# boitier_commande.net
KiCad netlist of a schematic drawn in Altium Designer
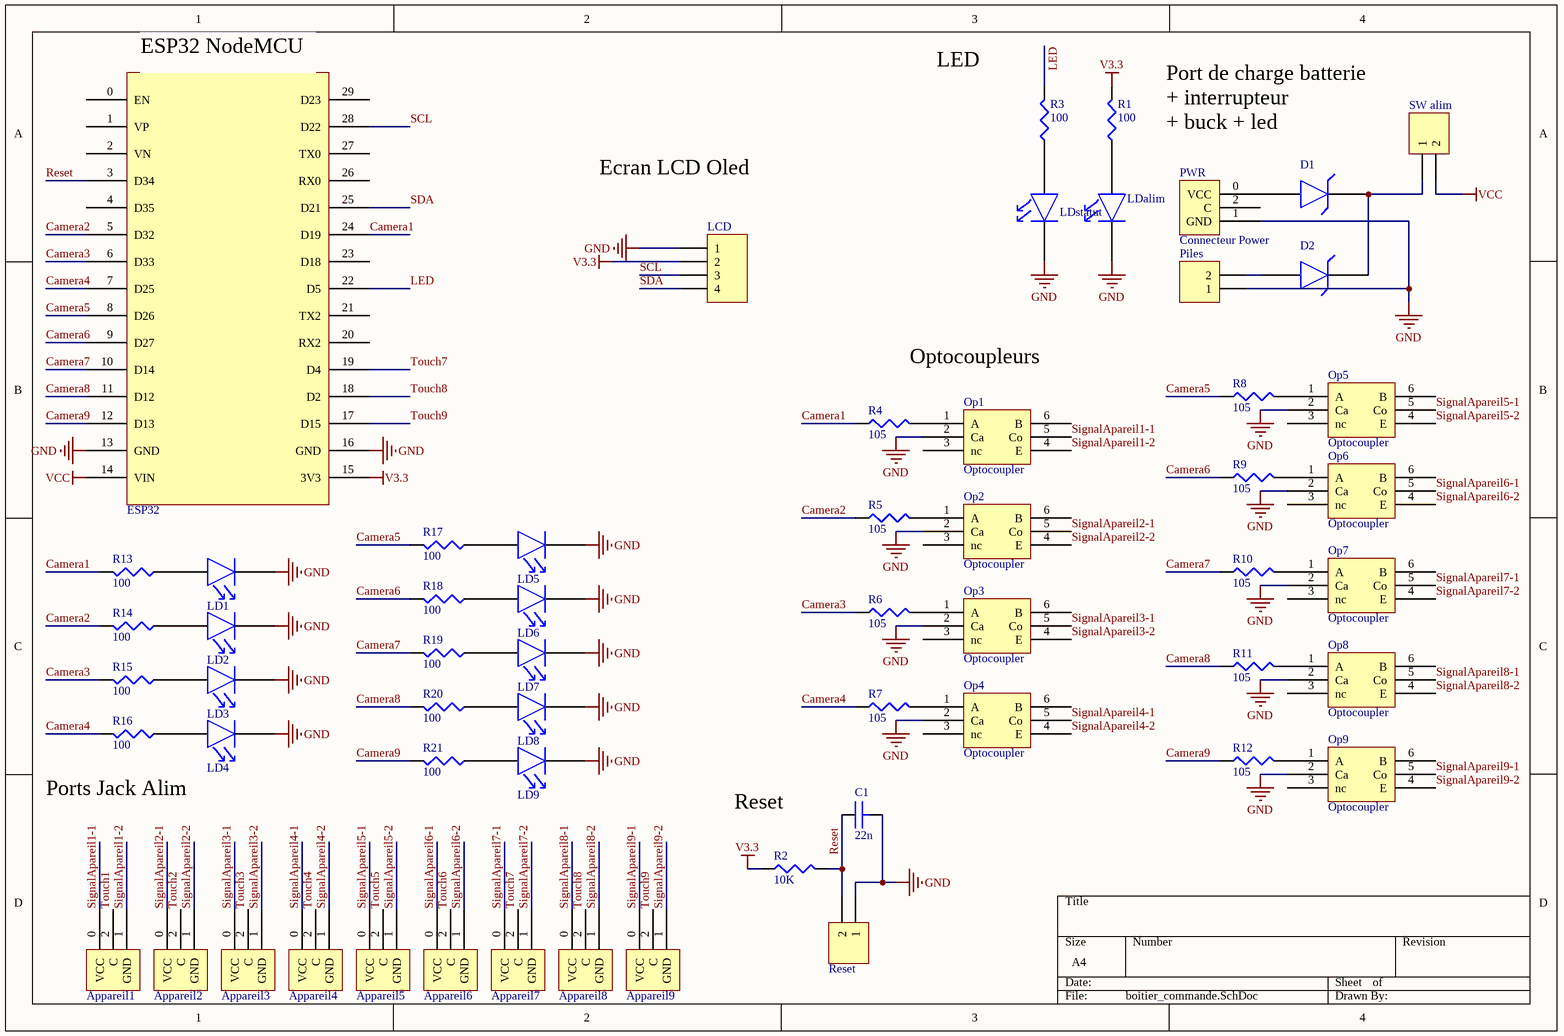
[diagram p0: boitier_commande.SchDoc]

(export (version "E")
  (design (tool "Eeschema 10.0.6"))
  (components
    (comp (ref "Appareil1")
      (value "Connecteur Power")
      (footprint "Connecteur Power")
      (libsource (lib "Jack Alim") (part "Connecteur Power"))
    )
    (comp (ref "Appareil2")
      (value "Connecteur Power")
      (footprint "Connecteur Power")
      (libsource (lib "Jack Alim") (part "Connecteur Power"))
    )
    (comp (ref "Appareil3")
      (value "Connecteur Power")
      (footprint "Connecteur Power")
      (libsource (lib "Jack Alim") (part "Connecteur Power"))
    )
    (comp (ref "Appareil4")
      (value "Connecteur Power")
      (footprint "Connecteur Power")
      (libsource (lib "Jack Alim") (part "Connecteur Power"))
    )
    (comp (ref "Appareil5")
      (value "Connecteur Power")
      (footprint "Connecteur Power")
      (libsource (lib "Jack Alim") (part "Connecteur Power"))
    )
    (comp (ref "Appareil6")
      (value "Connecteur Power")
      (footprint "Connecteur Power")
      (libsource (lib "Jack Alim") (part "Connecteur Power"))
    )
    (comp (ref "Appareil7")
      (value "Connecteur Power")
      (footprint "Connecteur Power")
      (libsource (lib "Jack Alim") (part "Connecteur Power"))
    )
    (comp (ref "Appareil8")
      (value "Connecteur Power")
      (footprint "Connecteur Power")
      (libsource (lib "Jack Alim") (part "Connecteur Power"))
    )
    (comp (ref "Appareil9")
      (value "Connecteur Power")
      (footprint "Connecteur Power")
      (libsource (lib "Jack Alim") (part "Connecteur Power"))
    )
    (comp (ref "C1")
      (value "22n")
      (footprint "RAD0.1")
      (description "capacité non polarisée")
      (fields (field (name "Comment") "CAP"))
      (libsource (lib "ISEN_basics") (part "CAP"))
    )
    (comp (ref "D1")
      (value "comment")
      (footprint "DIODE0.4")
      (description "diode schottky standard")
      (libsource (lib "ISEN_basics") (part "DIODE_schottky"))
    )
    (comp (ref "D2")
      (value "comment")
      (footprint "DIODE0.4")
      (description "diode schottky standard")
      (libsource (lib "ISEN_basics") (part "DIODE_schottky"))
    )
    (comp (ref "ESP32")
      (value "ESP32devKit")
      (footprint "ESP32")
      (libsource (lib "ESP32") (part "ESP32devKit"))
    )
    (comp (ref "LCD")
      (value "OLED LCD")
      (footprint "HDR1X4")
      (description "Header, 4-Pin")
      (fields (field (name "PUBLISHER") "Altium Limited"))
      (libsource (lib "Miscellaneous Connectors") (part "Header 4"))
    )
    (comp (ref "LD1")
      (value "comment")
      (footprint "LED0805")
      (description "LED 5mm/3mm/CMS")
      (libsource (lib "ISEN_basics") (part "LED"))
    )
    (comp (ref "LD2")
      (value "comment")
      (footprint "LED0805")
      (description "LED 5mm/3mm/CMS")
      (libsource (lib "ISEN_basics") (part "LED"))
    )
    (comp (ref "LD3")
      (value "comment")
      (footprint "LED0805")
      (description "LED 5mm/3mm/CMS")
      (libsource (lib "ISEN_basics") (part "LED"))
    )
    (comp (ref "LD4")
      (value "comment")
      (footprint "LED0805")
      (description "LED 5mm/3mm/CMS")
      (libsource (lib "ISEN_basics") (part "LED"))
    )
    (comp (ref "LD5")
      (value "comment")
      (footprint "LED0805")
      (description "LED 5mm/3mm/CMS")
      (libsource (lib "ISEN_basics") (part "LED"))
    )
    (comp (ref "LD6")
      (value "comment")
      (footprint "LED0805")
      (description "LED 5mm/3mm/CMS")
      (libsource (lib "ISEN_basics") (part "LED"))
    )
    (comp (ref "LD7")
      (value "comment")
      (footprint "LED0805")
      (description "LED 5mm/3mm/CMS")
      (libsource (lib "ISEN_basics") (part "LED"))
    )
    (comp (ref "LD8")
      (value "comment")
      (footprint "LED0805")
      (description "LED 5mm/3mm/CMS")
      (libsource (lib "ISEN_basics") (part "LED"))
    )
    (comp (ref "LD9")
      (value "comment")
      (footprint "LED0805")
      (description "LED 5mm/3mm/CMS")
      (libsource (lib "ISEN_basics") (part "LED"))
    )
    (comp (ref "LDalim")
      (value "comment")
      (footprint "LED3")
      (description "LED 5mm/3mm/CMS")
      (libsource (lib "ISEN_basics") (part "LED"))
    )
    (comp (ref "LDstatut")
      (value "comment")
      (footprint "LED3")
      (description "LED 5mm/3mm/CMS")
      (libsource (lib "ISEN_basics") (part "LED"))
    )
    (comp (ref "Op1")
      (value "Optocoupler")
      (footprint "4N26")
      (libsource (lib "Optocoupleur") (part "Optocoupler"))
    )
    (comp (ref "Op2")
      (value "Optocoupler")
      (footprint "4N26")
      (libsource (lib "Optocoupleur") (part "Optocoupler"))
    )
    (comp (ref "Op3")
      (value "Optocoupler")
      (footprint "4N26")
      (libsource (lib "Optocoupleur") (part "Optocoupler"))
    )
    (comp (ref "Op4")
      (value "Optocoupler")
      (footprint "4N26")
      (libsource (lib "Optocoupleur") (part "Optocoupler"))
    )
    (comp (ref "Op5")
      (value "Optocoupler")
      (footprint "4N26")
      (libsource (lib "Optocoupleur") (part "Optocoupler"))
    )
    (comp (ref "Op6")
      (value "Optocoupler")
      (footprint "4N26")
      (libsource (lib "Optocoupleur") (part "Optocoupler"))
    )
    (comp (ref "Op7")
      (value "Optocoupler")
      (footprint "4N26")
      (libsource (lib "Optocoupleur") (part "Optocoupler"))
    )
    (comp (ref "Op8")
      (value "Optocoupler")
      (footprint "4N26")
      (libsource (lib "Optocoupleur") (part "Optocoupler"))
    )
    (comp (ref "Op9")
      (value "Optocoupler")
      (footprint "4N26")
      (libsource (lib "Optocoupleur") (part "Optocoupler"))
    )
    (comp (ref "Piles")
      (value "Header 2")
      (footprint "HDR1X2")
      (description "Header, 2-Pin")
      (fields (field (name "PUBLISHER") "Altium Limited"))
      (libsource (lib "") (part "Header 2_1"))
    )
    (comp (ref "PWR")
      (value "Connecteur Power")
      (footprint "Connecteur Power")
      (libsource (lib "") (part "Connecteur Power_1"))
    )
    (comp (ref "R1")
      (value "100")
      (footprint "AXIAL0.4")
      (description "resistance")
      (fields (field (name "Comment") "RES"))
      (libsource (lib "ISEN_basics") (part "RES"))
    )
    (comp (ref "R2")
      (value "10K")
      (footprint "AXIAL0.4")
      (description "resistance")
      (fields (field (name "Comment") "RES"))
      (libsource (lib "ISEN_basics") (part "RES"))
    )
    (comp (ref "R3")
      (value "100")
      (footprint "AXIAL0.4")
      (description "resistance")
      (fields (field (name "Comment") "RES"))
      (libsource (lib "ISEN_basics") (part "RES"))
    )
    (comp (ref "R4")
      (value "105")
      (footprint "AXIAL0.4")
      (description "resistance")
      (fields (field (name "Comment") "RES"))
      (libsource (lib "ISEN_basics") (part "RES"))
    )
    (comp (ref "R5")
      (value "105")
      (footprint "AXIAL0.4")
      (description "resistance")
      (fields (field (name "Comment") "RES"))
      (libsource (lib "ISEN_basics") (part "RES"))
    )
    (comp (ref "R6")
      (value "105")
      (footprint "AXIAL0.4")
      (description "resistance")
      (fields (field (name "Comment") "RES"))
      (libsource (lib "ISEN_basics") (part "RES"))
    )
    (comp (ref "R7")
      (value "105")
      (footprint "AXIAL0.4")
      (description "resistance")
      (fields (field (name "Comment") "RES"))
      (libsource (lib "ISEN_basics") (part "RES"))
    )
    (comp (ref "R8")
      (value "105")
      (footprint "AXIAL0.4")
      (description "resistance")
      (fields (field (name "Comment") "RES"))
      (libsource (lib "ISEN_basics") (part "RES"))
    )
    (comp (ref "R9")
      (value "105")
      (footprint "AXIAL0.4")
      (description "resistance")
      (fields (field (name "Comment") "RES"))
      (libsource (lib "ISEN_basics") (part "RES"))
    )
    (comp (ref "R10")
      (value "105")
      (footprint "AXIAL0.4")
      (description "resistance")
      (fields (field (name "Comment") "RES"))
      (libsource (lib "ISEN_basics") (part "RES"))
    )
    (comp (ref "R11")
      (value "105")
      (footprint "AXIAL0.4")
      (description "resistance")
      (fields (field (name "Comment") "RES"))
      (libsource (lib "ISEN_basics") (part "RES"))
    )
    (comp (ref "R12")
      (value "105")
      (footprint "AXIAL0.4")
      (description "resistance")
      (fields (field (name "Comment") "RES"))
      (libsource (lib "ISEN_basics") (part "RES"))
    )
    (comp (ref "R13")
      (value "100")
      (footprint "0805")
      (description "resistance")
      (fields (field (name "Comment") "RES"))
      (libsource (lib "ISEN_basics") (part "RES"))
    )
    (comp (ref "R14")
      (value "100")
      (footprint "0805")
      (description "resistance")
      (fields (field (name "Comment") "RES"))
      (libsource (lib "ISEN_basics") (part "RES"))
    )
    (comp (ref "R15")
      (value "100")
      (footprint "0805")
      (description "resistance")
      (fields (field (name "Comment") "RES"))
      (libsource (lib "ISEN_basics") (part "RES"))
    )
    (comp (ref "R16")
      (value "100")
      (footprint "0805")
      (description "resistance")
      (fields (field (name "Comment") "RES"))
      (libsource (lib "ISEN_basics") (part "RES"))
    )
    (comp (ref "R17")
      (value "100")
      (footprint "0805")
      (description "resistance")
      (fields (field (name "Comment") "RES"))
      (libsource (lib "ISEN_basics") (part "RES"))
    )
    (comp (ref "R18")
      (value "100")
      (footprint "0805")
      (description "resistance")
      (fields (field (name "Comment") "RES"))
      (libsource (lib "ISEN_basics") (part "RES"))
    )
    (comp (ref "R19")
      (value "100")
      (footprint "0805")
      (description "resistance")
      (fields (field (name "Comment") "RES"))
      (libsource (lib "ISEN_basics") (part "RES"))
    )
    (comp (ref "R20")
      (value "100")
      (footprint "0805")
      (description "resistance")
      (fields (field (name "Comment") "RES"))
      (libsource (lib "ISEN_basics") (part "RES"))
    )
    (comp (ref "R21")
      (value "100")
      (footprint "0805")
      (description "resistance")
      (fields (field (name "Comment") "RES"))
      (libsource (lib "ISEN_basics") (part "RES"))
    )
    (comp (ref "Reset")
      (value "Header 2")
      (footprint "HDR1X2")
      (description "Header, 2-Pin")
      (fields (field (name "PUBLISHER") "Altium Limited"))
      (libsource (lib "") (part "Header 2_2"))
    )
    (comp (ref "SW alim")
      (value "Header 2")
      (footprint "HDR1X2")
      (description "Header, 2-Pin")
      (fields (field (name "PUBLISHER") "Altium Limited"))
      (libsource (lib "Miscellaneous Connectors") (part "Header 2"))
    )
  )
  (nets
    (net (code "1") (name "/Camera1") (class "Default")
      (node (ref "ESP32") (pin "24") (pinfunction "D19_24") (pintype "passive"))
      (node (ref "R13") (pin "2") (pintype "passive"))
      (node (ref "R4") (pin "1") (pintype "passive"))
    )
    (net (code "2") (name "/Camera2") (class "Default")
      (node (ref "ESP32") (pin "5") (pinfunction "D32_5") (pintype "passive"))
      (node (ref "R14") (pin "2") (pintype "passive"))
      (node (ref "R5") (pin "1") (pintype "passive"))
    )
    (net (code "3") (name "/Camera3") (class "Default")
      (node (ref "ESP32") (pin "6") (pinfunction "D33_6") (pintype "passive"))
      (node (ref "R15") (pin "2") (pintype "passive"))
      (node (ref "R6") (pin "1") (pintype "passive"))
    )
    (net (code "4") (name "/Camera4") (class "Default")
      (node (ref "ESP32") (pin "7") (pinfunction "D25_7") (pintype "passive"))
      (node (ref "R16") (pin "2") (pintype "passive"))
      (node (ref "R7") (pin "1") (pintype "passive"))
    )
    (net (code "5") (name "/Camera5") (class "Default")
      (node (ref "ESP32") (pin "8") (pinfunction "D26_8") (pintype "passive"))
      (node (ref "R17") (pin "2") (pintype "passive"))
      (node (ref "R8") (pin "1") (pintype "passive"))
    )
    (net (code "6") (name "/Camera6") (class "Default")
      (node (ref "ESP32") (pin "9") (pinfunction "D27_9") (pintype "passive"))
      (node (ref "R18") (pin "2") (pintype "passive"))
      (node (ref "R9") (pin "1") (pintype "passive"))
    )
    (net (code "7") (name "/Camera7") (class "Default")
      (node (ref "ESP32") (pin "10") (pinfunction "D14_10") (pintype "passive"))
      (node (ref "R10") (pin "1") (pintype "passive"))
      (node (ref "R19") (pin "2") (pintype "passive"))
    )
    (net (code "8") (name "/Camera8") (class "Default")
      (node (ref "ESP32") (pin "11") (pinfunction "D12_11") (pintype "passive"))
      (node (ref "R11") (pin "1") (pintype "passive"))
      (node (ref "R20") (pin "2") (pintype "passive"))
    )
    (net (code "9") (name "/Camera9") (class "Default")
      (node (ref "ESP32") (pin "12") (pinfunction "D13_12") (pintype "passive"))
      (node (ref "R12") (pin "1") (pintype "passive"))
      (node (ref "R21") (pin "2") (pintype "passive"))
    )
    (net (code "10") (name "/LED") (class "Default")
      (node (ref "ESP32") (pin "22") (pinfunction "D5_22") (pintype "passive"))
      (node (ref "R3") (pin "2") (pintype "passive"))
    )
    (net (code "11") (name "/Reset") (class "Default")
      (node (ref "C1") (pin "1") (pinfunction "1_1") (pintype "passive"))
      (node (ref "ESP32") (pin "3") (pinfunction "D34_3") (pintype "passive"))
      (node (ref "R2") (pin "2") (pintype "passive"))
      (node (ref "Reset") (pin "2") (pinfunction "2_2") (pintype "passive"))
    )
    (net (code "12") (name "/SCL") (class "Default")
      (node (ref "ESP32") (pin "28") (pinfunction "D22_28") (pintype "passive"))
      (node (ref "LCD") (pin "3") (pinfunction "3_3") (pintype "passive"))
    )
    (net (code "13") (name "/SDA") (class "Default")
      (node (ref "ESP32") (pin "25") (pinfunction "D21_25") (pintype "passive"))
      (node (ref "LCD") (pin "4") (pinfunction "4_4") (pintype "passive"))
    )
    (net (code "14") (name "/SignalApareil1-1") (class "Default")
      (node (ref "Appareil1") (pin "0") (pinfunction "VCC_0") (pintype "passive"))
      (node (ref "Op1") (pin "5") (pinfunction "Co_5") (pintype "passive"))
    )
    (net (code "15") (name "/SignalApareil1-2") (class "Default")
      (node (ref "Appareil1") (pin "1") (pinfunction "GND_1") (pintype "passive"))
      (node (ref "Op1") (pin "4") (pinfunction "E_4") (pintype "passive"))
    )
    (net (code "16") (name "/SignalApareil2-1") (class "Default")
      (node (ref "Appareil2") (pin "0") (pinfunction "VCC_0") (pintype "passive"))
      (node (ref "Op2") (pin "5") (pinfunction "Co_5") (pintype "passive"))
    )
    (net (code "17") (name "/SignalApareil2-2") (class "Default")
      (node (ref "Appareil2") (pin "1") (pinfunction "GND_1") (pintype "passive"))
      (node (ref "Op2") (pin "4") (pinfunction "E_4") (pintype "passive"))
    )
    (net (code "18") (name "/SignalApareil3-1") (class "Default")
      (node (ref "Appareil3") (pin "0") (pinfunction "VCC_0") (pintype "passive"))
      (node (ref "Op3") (pin "5") (pinfunction "Co_5") (pintype "passive"))
    )
    (net (code "19") (name "/SignalApareil3-2") (class "Default")
      (node (ref "Appareil3") (pin "1") (pinfunction "GND_1") (pintype "passive"))
      (node (ref "Op3") (pin "4") (pinfunction "E_4") (pintype "passive"))
    )
    (net (code "20") (name "/SignalApareil4-1") (class "Default")
      (node (ref "Appareil4") (pin "0") (pinfunction "VCC_0") (pintype "passive"))
      (node (ref "Op4") (pin "5") (pinfunction "Co_5") (pintype "passive"))
    )
    (net (code "21") (name "/SignalApareil4-2") (class "Default")
      (node (ref "Appareil4") (pin "1") (pinfunction "GND_1") (pintype "passive"))
      (node (ref "Op4") (pin "4") (pinfunction "E_4") (pintype "passive"))
    )
    (net (code "22") (name "/SignalApareil5-1") (class "Default")
      (node (ref "Appareil5") (pin "0") (pinfunction "VCC_0") (pintype "passive"))
      (node (ref "Op5") (pin "5") (pinfunction "Co_5") (pintype "passive"))
    )
    (net (code "23") (name "/SignalApareil5-2") (class "Default")
      (node (ref "Appareil5") (pin "1") (pinfunction "GND_1") (pintype "passive"))
      (node (ref "Op5") (pin "4") (pinfunction "E_4") (pintype "passive"))
    )
    (net (code "24") (name "/SignalApareil6-1") (class "Default")
      (node (ref "Appareil6") (pin "0") (pinfunction "VCC_0") (pintype "passive"))
      (node (ref "Op6") (pin "5") (pinfunction "Co_5") (pintype "passive"))
    )
    (net (code "25") (name "/SignalApareil6-2") (class "Default")
      (node (ref "Appareil6") (pin "1") (pinfunction "GND_1") (pintype "passive"))
      (node (ref "Op6") (pin "4") (pinfunction "E_4") (pintype "passive"))
    )
    (net (code "26") (name "/SignalApareil7-1") (class "Default")
      (node (ref "Appareil7") (pin "0") (pinfunction "VCC_0") (pintype "passive"))
      (node (ref "Op7") (pin "5") (pinfunction "Co_5") (pintype "passive"))
    )
    (net (code "27") (name "/SignalApareil7-2") (class "Default")
      (node (ref "Appareil7") (pin "1") (pinfunction "GND_1") (pintype "passive"))
      (node (ref "Op7") (pin "4") (pinfunction "E_4") (pintype "passive"))
    )
    (net (code "28") (name "/SignalApareil8-1") (class "Default")
      (node (ref "Appareil8") (pin "0") (pinfunction "VCC_0") (pintype "passive"))
      (node (ref "Op8") (pin "5") (pinfunction "Co_5") (pintype "passive"))
    )
    (net (code "29") (name "/SignalApareil8-2") (class "Default")
      (node (ref "Appareil8") (pin "1") (pinfunction "GND_1") (pintype "passive"))
      (node (ref "Op8") (pin "4") (pinfunction "E_4") (pintype "passive"))
    )
    (net (code "30") (name "/SignalApareil9-1") (class "Default")
      (node (ref "Appareil9") (pin "0") (pinfunction "VCC_0") (pintype "passive"))
      (node (ref "Op9") (pin "5") (pinfunction "Co_5") (pintype "passive"))
    )
    (net (code "31") (name "/SignalApareil9-2") (class "Default")
      (node (ref "Appareil9") (pin "1") (pinfunction "GND_1") (pintype "passive"))
      (node (ref "Op9") (pin "4") (pinfunction "E_4") (pintype "passive"))
    )
    (net (code "32") (name "/Touch1") (class "Default")
      (node (ref "Appareil1") (pin "2") (pinfunction "C_2") (pintype "passive"))
    )
    (net (code "33") (name "/Touch2") (class "Default")
      (node (ref "Appareil2") (pin "2") (pinfunction "C_2") (pintype "passive"))
    )
    (net (code "34") (name "/Touch3") (class "Default")
      (node (ref "Appareil3") (pin "2") (pinfunction "C_2") (pintype "passive"))
    )
    (net (code "35") (name "/Touch4") (class "Default")
      (node (ref "Appareil4") (pin "2") (pinfunction "C_2") (pintype "passive"))
    )
    (net (code "36") (name "/Touch5") (class "Default")
      (node (ref "Appareil5") (pin "2") (pinfunction "C_2") (pintype "passive"))
    )
    (net (code "37") (name "/Touch6") (class "Default")
      (node (ref "Appareil6") (pin "2") (pinfunction "C_2") (pintype "passive"))
    )
    (net (code "38") (name "/Touch7") (class "Default")
      (node (ref "Appareil7") (pin "2") (pinfunction "C_2") (pintype "passive"))
      (node (ref "ESP32") (pin "19") (pinfunction "D4_19") (pintype "passive"))
    )
    (net (code "39") (name "/Touch8") (class "Default")
      (node (ref "Appareil8") (pin "2") (pinfunction "C_2") (pintype "passive"))
      (node (ref "ESP32") (pin "18") (pinfunction "D2_18") (pintype "passive"))
    )
    (net (code "40") (name "/Touch9") (class "Default")
      (node (ref "Appareil9") (pin "2") (pinfunction "C_2") (pintype "passive"))
      (node (ref "ESP32") (pin "17") (pinfunction "D15_17") (pintype "passive"))
    )
    (net (code "41") (name "GND") (class "Default")
      (node (ref "C1") (pin "2") (pinfunction "2_2") (pintype "passive"))
      (node (ref "ESP32") (pin "13") (pinfunction "GND_13") (pintype "passive"))
      (node (ref "ESP32") (pin "16") (pinfunction "GND_16") (pintype "passive"))
      (node (ref "LCD") (pin "1") (pinfunction "1_1") (pintype "passive"))
      (node (ref "LD1") (pin "K") (pinfunction "10_K") (pintype "passive"))
      (node (ref "LD2") (pin "K") (pinfunction "10_K") (pintype "passive"))
      (node (ref "LD3") (pin "K") (pinfunction "10_K") (pintype "passive"))
      (node (ref "LD4") (pin "K") (pinfunction "10_K") (pintype "passive"))
      (node (ref "LD5") (pin "K") (pinfunction "10_K") (pintype "passive"))
      (node (ref "LD6") (pin "K") (pinfunction "10_K") (pintype "passive"))
      (node (ref "LD7") (pin "K") (pinfunction "10_K") (pintype "passive"))
      (node (ref "LD8") (pin "K") (pinfunction "10_K") (pintype "passive"))
      (node (ref "LD9") (pin "K") (pinfunction "10_K") (pintype "passive"))
      (node (ref "LDalim") (pin "K") (pinfunction "10_K") (pintype "passive"))
      (node (ref "LDstatut") (pin "K") (pinfunction "10_K") (pintype "passive"))
      (node (ref "Op1") (pin "2") (pinfunction "Ca_2") (pintype "passive"))
      (node (ref "Op2") (pin "2") (pinfunction "Ca_2") (pintype "passive"))
      (node (ref "Op3") (pin "2") (pinfunction "Ca_2") (pintype "passive"))
      (node (ref "Op4") (pin "2") (pinfunction "Ca_2") (pintype "passive"))
      (node (ref "Op5") (pin "2") (pinfunction "Ca_2") (pintype "passive"))
      (node (ref "Op6") (pin "2") (pinfunction "Ca_2") (pintype "passive"))
      (node (ref "Op7") (pin "2") (pinfunction "Ca_2") (pintype "passive"))
      (node (ref "Op8") (pin "2") (pinfunction "Ca_2") (pintype "passive"))
      (node (ref "Op9") (pin "2") (pinfunction "Ca_2") (pintype "passive"))
      (node (ref "PWR") (pin "1") (pinfunction "GND_1") (pintype "passive"))
      (node (ref "Piles") (pin "1") (pinfunction "1_1") (pintype "passive"))
      (node (ref "Reset") (pin "1") (pinfunction "1_1") (pintype "passive"))
    )
    (net (code "42") (name "Net-(D1-Pad2)") (class "Default")
      (node (ref "D1") (pin "2") (pinfunction "2_2") (pintype "passive"))
      (node (ref "D2") (pin "2") (pinfunction "2_2") (pintype "passive"))
      (node (ref "SW alim") (pin "1") (pinfunction "1_1") (pintype "passive"))
    )
    (net (code "43") (name "Net-(D2-Pad1)") (class "Default")
      (node (ref "D2") (pin "1") (pinfunction "1_1") (pintype "passive"))
      (node (ref "Piles") (pin "2") (pinfunction "2_2") (pintype "passive"))
    )
    (net (code "44") (name "Net-(LD1-8)") (class "Default")
      (node (ref "LD1") (pin "A") (pinfunction "8_A") (pintype "passive"))
      (node (ref "R13") (pin "1") (pintype "passive"))
    )
    (net (code "45") (name "Net-(LD2-8)") (class "Default")
      (node (ref "LD2") (pin "A") (pinfunction "8_A") (pintype "passive"))
      (node (ref "R14") (pin "1") (pintype "passive"))
    )
    (net (code "46") (name "Net-(LD3-8)") (class "Default")
      (node (ref "LD3") (pin "A") (pinfunction "8_A") (pintype "passive"))
      (node (ref "R15") (pin "1") (pintype "passive"))
    )
    (net (code "47") (name "Net-(LD4-8)") (class "Default")
      (node (ref "LD4") (pin "A") (pinfunction "8_A") (pintype "passive"))
      (node (ref "R16") (pin "1") (pintype "passive"))
    )
    (net (code "48") (name "Net-(LD5-8)") (class "Default")
      (node (ref "LD5") (pin "A") (pinfunction "8_A") (pintype "passive"))
      (node (ref "R17") (pin "1") (pintype "passive"))
    )
    (net (code "49") (name "Net-(LD6-8)") (class "Default")
      (node (ref "LD6") (pin "A") (pinfunction "8_A") (pintype "passive"))
      (node (ref "R18") (pin "1") (pintype "passive"))
    )
    (net (code "50") (name "Net-(LD7-8)") (class "Default")
      (node (ref "LD7") (pin "A") (pinfunction "8_A") (pintype "passive"))
      (node (ref "R19") (pin "1") (pintype "passive"))
    )
    (net (code "51") (name "Net-(LD8-8)") (class "Default")
      (node (ref "LD8") (pin "A") (pinfunction "8_A") (pintype "passive"))
      (node (ref "R20") (pin "1") (pintype "passive"))
    )
    (net (code "52") (name "Net-(LD9-8)") (class "Default")
      (node (ref "LD9") (pin "A") (pinfunction "8_A") (pintype "passive"))
      (node (ref "R21") (pin "1") (pintype "passive"))
    )
    (net (code "53") (name "Net-(LDalim-8)") (class "Default")
      (node (ref "LDalim") (pin "A") (pinfunction "8_A") (pintype "passive"))
      (node (ref "R1") (pin "1") (pintype "passive"))
    )
    (net (code "54") (name "Net-(LDstatut-8)") (class "Default")
      (node (ref "LDstatut") (pin "A") (pinfunction "8_A") (pintype "passive"))
      (node (ref "R3") (pin "1") (pintype "passive"))
    )
    (net (code "55") (name "Net-(Op1-A)") (class "Default")
      (node (ref "Op1") (pin "1") (pinfunction "A_1") (pintype "passive"))
      (node (ref "R4") (pin "2") (pintype "passive"))
    )
    (net (code "56") (name "Net-(Op2-A)") (class "Default")
      (node (ref "Op2") (pin "1") (pinfunction "A_1") (pintype "passive"))
      (node (ref "R5") (pin "2") (pintype "passive"))
    )
    (net (code "57") (name "Net-(Op3-A)") (class "Default")
      (node (ref "Op3") (pin "1") (pinfunction "A_1") (pintype "passive"))
      (node (ref "R6") (pin "2") (pintype "passive"))
    )
    (net (code "58") (name "Net-(Op4-A)") (class "Default")
      (node (ref "Op4") (pin "1") (pinfunction "A_1") (pintype "passive"))
      (node (ref "R7") (pin "2") (pintype "passive"))
    )
    (net (code "59") (name "Net-(Op5-A)") (class "Default")
      (node (ref "Op5") (pin "1") (pinfunction "A_1") (pintype "passive"))
      (node (ref "R8") (pin "2") (pintype "passive"))
    )
    (net (code "60") (name "Net-(Op6-A)") (class "Default")
      (node (ref "Op6") (pin "1") (pinfunction "A_1") (pintype "passive"))
      (node (ref "R9") (pin "2") (pintype "passive"))
    )
    (net (code "61") (name "Net-(Op7-A)") (class "Default")
      (node (ref "Op7") (pin "1") (pinfunction "A_1") (pintype "passive"))
      (node (ref "R10") (pin "2") (pintype "passive"))
    )
    (net (code "62") (name "Net-(Op8-A)") (class "Default")
      (node (ref "Op8") (pin "1") (pinfunction "A_1") (pintype "passive"))
      (node (ref "R11") (pin "2") (pintype "passive"))
    )
    (net (code "63") (name "Net-(Op9-A)") (class "Default")
      (node (ref "Op9") (pin "1") (pinfunction "A_1") (pintype "passive"))
      (node (ref "R12") (pin "2") (pintype "passive"))
    )
    (net (code "64") (name "Net-(PWR-VCC)") (class "Default")
      (node (ref "D1") (pin "1") (pinfunction "1_1") (pintype "passive"))
      (node (ref "PWR") (pin "0") (pinfunction "VCC_0") (pintype "passive"))
    )
    (net (code "65") (name "V3.3") (class "Default")
      (node (ref "ESP32") (pin "15") (pinfunction "3V3_15") (pintype "passive"))
      (node (ref "LCD") (pin "2") (pinfunction "2_2") (pintype "passive"))
      (node (ref "R1") (pin "2") (pintype "passive"))
      (node (ref "R2") (pin "1") (pintype "passive"))
    )
    (net (code "66") (name "VCC") (class "Default")
      (node (ref "ESP32") (pin "14") (pinfunction "VIN_14") (pintype "passive"))
      (node (ref "SW alim") (pin "2") (pinfunction "2_2") (pintype "passive"))
    )
    (net (code "67") (name "unconnected-(ESP32-D18-Pad23)") (class "Default")
      (node (ref "ESP32") (pin "23") (pinfunction "D18_23") (pintype "passive"))
    )
    (net (code "68") (name "unconnected-(ESP32-D23-Pad29)") (class "Default")
      (node (ref "ESP32") (pin "29") (pinfunction "D23_29") (pintype "passive"))
    )
    (net (code "69") (name "unconnected-(ESP32-D35-Pad4)") (class "Default")
      (node (ref "ESP32") (pin "4") (pinfunction "D35_4") (pintype "passive"))
    )
    (net (code "70") (name "unconnected-(ESP32-EN-Pad0)") (class "Default")
      (node (ref "ESP32") (pin "0") (pinfunction "EN_0") (pintype "passive"))
    )
    (net (code "71") (name "unconnected-(ESP32-RX0-Pad26)") (class "Default")
      (node (ref "ESP32") (pin "26") (pinfunction "RX0_26") (pintype "passive"))
    )
    (net (code "72") (name "unconnected-(ESP32-RX2-Pad20)") (class "Default")
      (node (ref "ESP32") (pin "20") (pinfunction "RX2_20") (pintype "passive"))
    )
    (net (code "73") (name "unconnected-(ESP32-TX0-Pad27)") (class "Default")
      (node (ref "ESP32") (pin "27") (pinfunction "TX0_27") (pintype "passive"))
    )
    (net (code "74") (name "unconnected-(ESP32-TX2-Pad21)") (class "Default")
      (node (ref "ESP32") (pin "21") (pinfunction "TX2_21") (pintype "passive"))
    )
    (net (code "75") (name "unconnected-(ESP32-VN-Pad2)") (class "Default")
      (node (ref "ESP32") (pin "2") (pinfunction "VN_2") (pintype "passive"))
    )
    (net (code "76") (name "unconnected-(ESP32-VP-Pad1)") (class "Default")
      (node (ref "ESP32") (pin "1") (pinfunction "VP_1") (pintype "passive"))
    )
    (net (code "77") (name "unconnected-(Op1-B-Pad6)") (class "Default")
      (node (ref "Op1") (pin "6") (pinfunction "B_6") (pintype "passive"))
    )
    (net (code "78") (name "unconnected-(Op1-nc-Pad3)") (class "Default")
      (node (ref "Op1") (pin "3") (pinfunction "nc_3") (pintype "passive"))
    )
    (net (code "79") (name "unconnected-(Op2-B-Pad6)") (class "Default")
      (node (ref "Op2") (pin "6") (pinfunction "B_6") (pintype "passive"))
    )
    (net (code "80") (name "unconnected-(Op2-nc-Pad3)") (class "Default")
      (node (ref "Op2") (pin "3") (pinfunction "nc_3") (pintype "passive"))
    )
    (net (code "81") (name "unconnected-(Op3-B-Pad6)") (class "Default")
      (node (ref "Op3") (pin "6") (pinfunction "B_6") (pintype "passive"))
    )
    (net (code "82") (name "unconnected-(Op3-nc-Pad3)") (class "Default")
      (node (ref "Op3") (pin "3") (pinfunction "nc_3") (pintype "passive"))
    )
    (net (code "83") (name "unconnected-(Op4-B-Pad6)") (class "Default")
      (node (ref "Op4") (pin "6") (pinfunction "B_6") (pintype "passive"))
    )
    (net (code "84") (name "unconnected-(Op4-nc-Pad3)") (class "Default")
      (node (ref "Op4") (pin "3") (pinfunction "nc_3") (pintype "passive"))
    )
    (net (code "85") (name "unconnected-(Op5-B-Pad6)") (class "Default")
      (node (ref "Op5") (pin "6") (pinfunction "B_6") (pintype "passive"))
    )
    (net (code "86") (name "unconnected-(Op5-nc-Pad3)") (class "Default")
      (node (ref "Op5") (pin "3") (pinfunction "nc_3") (pintype "passive"))
    )
    (net (code "87") (name "unconnected-(Op6-B-Pad6)") (class "Default")
      (node (ref "Op6") (pin "6") (pinfunction "B_6") (pintype "passive"))
    )
    (net (code "88") (name "unconnected-(Op6-nc-Pad3)") (class "Default")
      (node (ref "Op6") (pin "3") (pinfunction "nc_3") (pintype "passive"))
    )
    (net (code "89") (name "unconnected-(Op7-B-Pad6)") (class "Default")
      (node (ref "Op7") (pin "6") (pinfunction "B_6") (pintype "passive"))
    )
    (net (code "90") (name "unconnected-(Op7-nc-Pad3)") (class "Default")
      (node (ref "Op7") (pin "3") (pinfunction "nc_3") (pintype "passive"))
    )
    (net (code "91") (name "unconnected-(Op8-B-Pad6)") (class "Default")
      (node (ref "Op8") (pin "6") (pinfunction "B_6") (pintype "passive"))
    )
    (net (code "92") (name "unconnected-(Op8-nc-Pad3)") (class "Default")
      (node (ref "Op8") (pin "3") (pinfunction "nc_3") (pintype "passive"))
    )
    (net (code "93") (name "unconnected-(Op9-B-Pad6)") (class "Default")
      (node (ref "Op9") (pin "6") (pinfunction "B_6") (pintype "passive"))
    )
    (net (code "94") (name "unconnected-(Op9-nc-Pad3)") (class "Default")
      (node (ref "Op9") (pin "3") (pinfunction "nc_3") (pintype "passive"))
    )
    (net (code "95") (name "unconnected-(PWR-C-Pad2)") (class "Default")
      (node (ref "PWR") (pin "2") (pinfunction "C_2") (pintype "passive"))
    )
  )
)
